# lcd232.net
KiCad netlist of a schematic drawn in EAGLE
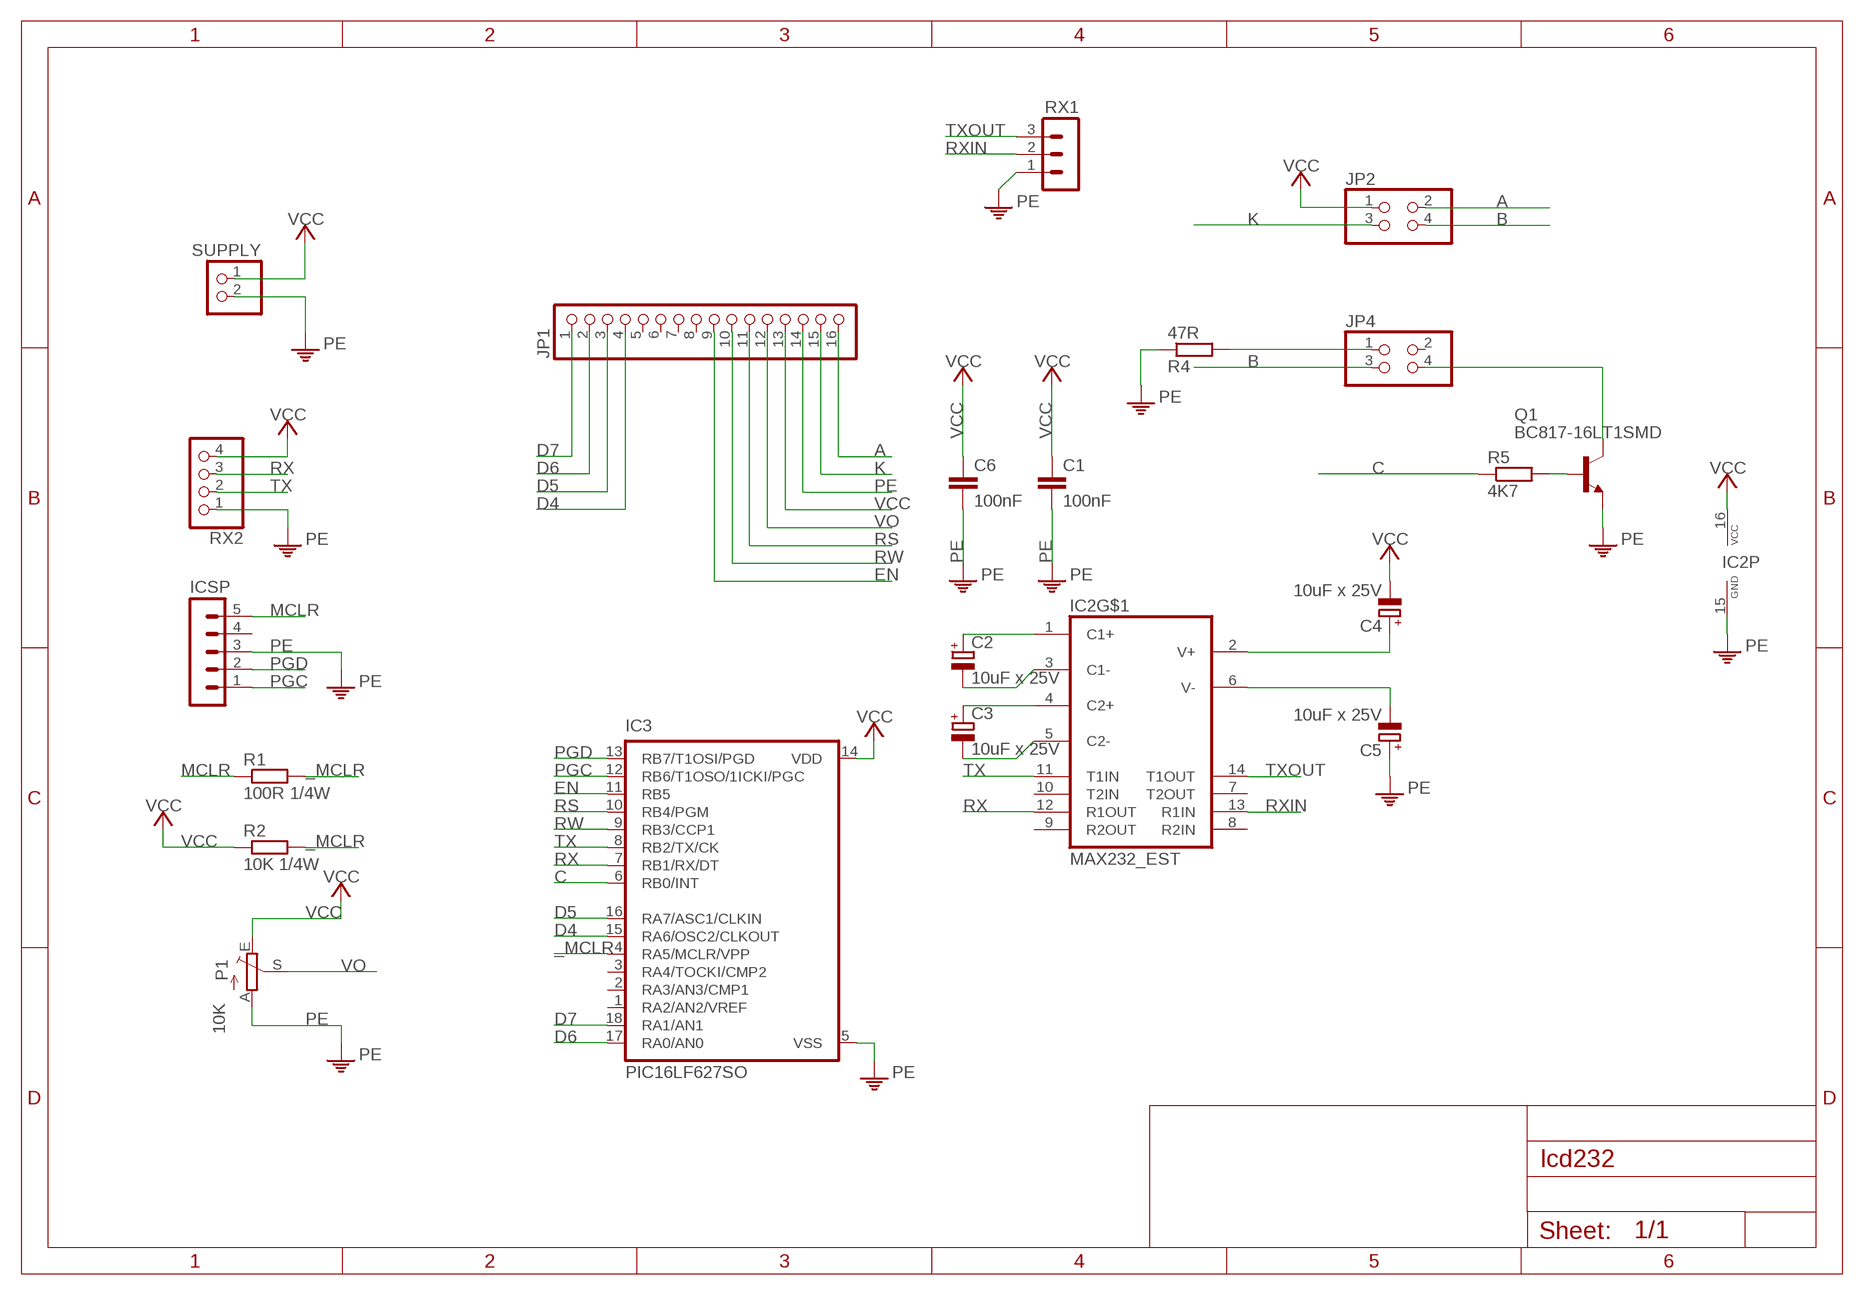
[diagram p0: schematic, sheet 1]

(export (version "E")
  (design (tool "Eeschema 10.0.6"))
  (components
    (comp (ref "C1")
      (value "100nF")
      (footprint "eagle-import:C0805")
      (libsource (lib "eagle-import") (part "C-EUC0805"))
    )
    (comp (ref "C2")
      (value "10uF x 25V")
      (footprint "eagle-import:E2-4")
      (libsource (lib "eagle-import") (part "CPOL-EUE2-4"))
    )
    (comp (ref "C3")
      (value "10uF x 25V")
      (footprint "eagle-import:E2-4")
      (libsource (lib "eagle-import") (part "CPOL-EUE2-4"))
    )
    (comp (ref "C4")
      (value "10uF x 25V")
      (footprint "eagle-import:E2-4")
      (libsource (lib "eagle-import") (part "CPOL-EUE2-4"))
    )
    (comp (ref "C5")
      (value "10uF x 25V")
      (footprint "eagle-import:E2-4")
      (libsource (lib "eagle-import") (part "CPOL-EUE2-4"))
    )
    (comp (ref "C6")
      (value "100nF")
      (footprint "eagle-import:C0805")
      (libsource (lib "eagle-import") (part "C-EUC0805"))
    )
    (comp (ref "IC2")
      (value "MAX232_EST")
      (footprint "eagle-import:SO16_EST")
      (libsource (lib "eagle-import") (part "MAX232_EST"))
    )
    (comp (ref "IC3")
      (value "PIC16LF627SO")
      (footprint "eagle-import:SO-18W")
      (fields (field (name "MF") "MICROCHIP") (field (name "MPN") "PIC16LF627A-I/SO"))
      (libsource (lib "eagle-import") (part "PIC16F627SOL"))
    )
    (comp (ref "ICSP")
      (value "MA05-1")
      (footprint "eagle-import:MA05-1")
      (libsource (lib "eagle-import") (part "MA05-1"))
    )
    (comp (ref "JP1")
      (value "PINHD-1X16")
      (footprint "eagle-import:1X16")
      (libsource (lib "eagle-import") (part "PINHD-1X16"))
    )
    (comp (ref "JP2")
      (value "PINHD-2X2")
      (footprint "eagle-import:2X02")
      (libsource (lib "eagle-import") (part "PINHD-2X2"))
    )
    (comp (ref "JP4")
      (value "PINHD-2X2")
      (footprint "eagle-import:2X02")
      (libsource (lib "eagle-import") (part "PINHD-2X2"))
    )
    (comp (ref "P1")
      (value "10K")
      (footprint "eagle-import:CA9V")
      (libsource (lib "eagle-import") (part "TRIM_EU-CA9V"))
    )
    (comp (ref "Q1")
      (value "BC817-16LT1SMD")
      (footprint "eagle-import:SOT23-BEC")
      (libsource (lib "eagle-import") (part "BC817SMD-16LT1"))
    )
    (comp (ref "R1")
      (value "100R 1/4W")
      (footprint "eagle-import:M0805")
      (libsource (lib "eagle-import") (part "R-EU_M0805"))
    )
    (comp (ref "R2")
      (value "10K 1/4W")
      (footprint "eagle-import:M0805")
      (libsource (lib "eagle-import") (part "R-EU_M0805"))
    )
    (comp (ref "R4")
      (value "47R")
      (footprint "eagle-import:M0805")
      (libsource (lib "eagle-import") (part "R-EU_M0805"))
    )
    (comp (ref "R5")
      (value "4K7")
      (footprint "eagle-import:M0805")
      (libsource (lib "eagle-import") (part "R-EU_M0805"))
    )
    (comp (ref "RX1")
      (value "MA03-1")
      (footprint "eagle-import:MA03-1")
      (fields (field (name "OC_FARNELL") "unknown") (field (name "OC_NEWARK") "unknown"))
      (libsource (lib "eagle-import") (part "MA03-1"))
    )
    (comp (ref "RX2")
      (value "PINHD-1X4")
      (footprint "eagle-import:1X04")
      (libsource (lib "eagle-import") (part "PINHD-1X4"))
    )
    (comp (ref "SUPPLY")
      (value "PINHD-1X2")
      (footprint "eagle-import:1X02")
      (libsource (lib "eagle-import") (part "PINHD-1X2"))
    )
  )
  (nets
    (net (code "1") (name "/A") (class "Default")
      (node (ref "JP1") (pin "16") (pinfunction "16_16") (pintype "passive"))
      (node (ref "JP2") (pin "2") (pinfunction "2_2") (pintype "passive"))
    )
    (net (code "2") (name "/B") (class "Default")
      (node (ref "JP2") (pin "4") (pinfunction "4_4") (pintype "passive"))
      (node (ref "JP4") (pin "3") (pinfunction "3_3") (pintype "passive"))
    )
    (net (code "3") (name "/C") (class "Default")
      (node (ref "IC3") (pin "6") (pinfunction "RB0/INT_6") (pintype "bidirectional"))
      (node (ref "R5") (pin "1") (pinfunction "1_1") (pintype "passive"))
    )
    (net (code "4") (name "/D4") (class "Default")
      (node (ref "IC3") (pin "15") (pinfunction "RA6/OSC2/CLKOUT_15") (pintype "bidirectional"))
      (node (ref "JP1") (pin "4") (pinfunction "4_4") (pintype "passive"))
    )
    (net (code "5") (name "/D5") (class "Default")
      (node (ref "IC3") (pin "16") (pinfunction "RA7/ASC1/CLKIN_16") (pintype "bidirectional"))
      (node (ref "JP1") (pin "3") (pinfunction "3_3") (pintype "passive"))
    )
    (net (code "6") (name "/D6") (class "Default")
      (node (ref "IC3") (pin "17") (pinfunction "RA0/AN0_17") (pintype "bidirectional"))
      (node (ref "JP1") (pin "2") (pinfunction "2_2") (pintype "passive"))
    )
    (net (code "7") (name "/D7") (class "Default")
      (node (ref "IC3") (pin "18") (pinfunction "RA1/AN1_18") (pintype "bidirectional"))
      (node (ref "JP1") (pin "1") (pinfunction "1_1") (pintype "passive"))
    )
    (net (code "8") (name "/EN") (class "Default")
      (node (ref "IC3") (pin "11") (pinfunction "RB5_11") (pintype "bidirectional"))
      (node (ref "JP1") (pin "9") (pinfunction "9_9") (pintype "passive"))
    )
    (net (code "9") (name "/K") (class "Default")
      (node (ref "JP1") (pin "15") (pinfunction "15_15") (pintype "passive"))
      (node (ref "JP2") (pin "3") (pinfunction "3_3") (pintype "passive"))
    )
    (net (code "10") (name "/MCLR") (class "Default")
      (node (ref "ICSP") (pin "5") (pinfunction "5_5") (pintype "passive"))
      (node (ref "R1") (pin "1") (pinfunction "1_1") (pintype "passive"))
    )
    (net (code "11") (name "/PGC") (class "Default")
      (node (ref "IC3") (pin "12") (pinfunction "RB6/T1OSO/1ICKI/PGC_12") (pintype "bidirectional"))
      (node (ref "ICSP") (pin "1") (pinfunction "1_1") (pintype "passive"))
    )
    (net (code "12") (name "/PGD") (class "Default")
      (node (ref "IC3") (pin "13") (pinfunction "RB7/T1OSI/PGD_13") (pintype "bidirectional"))
      (node (ref "ICSP") (pin "2") (pinfunction "2_2") (pintype "passive"))
    )
    (net (code "13") (name "/RS") (class "Default")
      (node (ref "IC3") (pin "10") (pinfunction "RB4/PGM_10") (pintype "bidirectional"))
      (node (ref "JP1") (pin "11") (pinfunction "11_11") (pintype "passive"))
    )
    (net (code "14") (name "/RW") (class "Default")
      (node (ref "IC3") (pin "9") (pinfunction "RB3/CCP1_9") (pintype "bidirectional"))
      (node (ref "JP1") (pin "10") (pinfunction "10_10") (pintype "passive"))
    )
    (net (code "15") (name "/RX") (class "Default")
      (node (ref "IC2") (pin "12") (pinfunction "R1OUT_12") (pintype "output"))
      (node (ref "IC3") (pin "7") (pinfunction "RB1/RX/DT_7") (pintype "bidirectional"))
      (node (ref "RX2") (pin "3") (pinfunction "3_3") (pintype "passive"))
    )
    (net (code "16") (name "/RXIN") (class "Default")
      (node (ref "IC2") (pin "13") (pinfunction "R1IN_13") (pintype "input"))
      (node (ref "RX1") (pin "2") (pinfunction "2_2") (pintype "passive"))
    )
    (net (code "17") (name "/TX") (class "Default")
      (node (ref "IC2") (pin "11") (pinfunction "T1IN_11") (pintype "input"))
      (node (ref "IC3") (pin "8") (pinfunction "RB2/TX/CK_8") (pintype "bidirectional"))
      (node (ref "RX2") (pin "2") (pinfunction "2_2") (pintype "passive"))
    )
    (net (code "18") (name "/TXOUT") (class "Default")
      (node (ref "IC2") (pin "14") (pinfunction "T1OUT_14") (pintype "output"))
      (node (ref "RX1") (pin "3") (pinfunction "3_3") (pintype "passive"))
    )
    (net (code "19") (name "/VO") (class "Default")
      (node (ref "JP1") (pin "12") (pinfunction "12_12") (pintype "passive"))
      (node (ref "P1") (pin "S") (pinfunction "S_S") (pintype "passive"))
    )
    (net (code "20") (name "/_MCLR") (class "Default")
      (node (ref "IC3") (pin "4") (pinfunction "RA5/MCLR/VPP_4") (pintype "input"))
      (node (ref "R1") (pin "2") (pinfunction "2_2") (pintype "passive"))
      (node (ref "R2") (pin "2") (pinfunction "2_2") (pintype "passive"))
    )
    (net (code "21") (name "Net-(IC2A-C1+)") (class "Default")
      (node (ref "C2") (pin "+") (pinfunction "+_+") (pintype "passive"))
      (node (ref "IC2") (pin "1") (pinfunction "C1+_1") (pintype "bidirectional"))
    )
    (net (code "22") (name "Net-(IC2A-C1-)") (class "Default")
      (node (ref "C2") (pin "-") (pinfunction "-_-") (pintype "passive"))
      (node (ref "IC2") (pin "3") (pinfunction "C1-_3") (pintype "bidirectional"))
    )
    (net (code "23") (name "Net-(IC2A-C2+)") (class "Default")
      (node (ref "C3") (pin "+") (pinfunction "+_+") (pintype "passive"))
      (node (ref "IC2") (pin "4") (pinfunction "C2+_4") (pintype "bidirectional"))
    )
    (net (code "24") (name "Net-(IC2A-C2-)") (class "Default")
      (node (ref "C3") (pin "-") (pinfunction "-_-") (pintype "passive"))
      (node (ref "IC2") (pin "5") (pinfunction "C2-_5") (pintype "bidirectional"))
    )
    (net (code "25") (name "Net-(IC2A-V+)") (class "Default")
      (node (ref "C4") (pin "+") (pinfunction "+_+") (pintype "passive"))
      (node (ref "IC2") (pin "2") (pinfunction "V+_2") (pintype "bidirectional"))
    )
    (net (code "26") (name "Net-(IC2A-V-)") (class "Default")
      (node (ref "C5") (pin "-") (pinfunction "-_-") (pintype "passive"))
      (node (ref "IC2") (pin "6") (pinfunction "V-_6") (pintype "bidirectional"))
    )
    (net (code "27") (name "Net-(JP4-Pad1)") (class "Default")
      (node (ref "JP4") (pin "1") (pinfunction "1_1") (pintype "passive"))
      (node (ref "R4") (pin "2") (pinfunction "2_2") (pintype "passive"))
    )
    (net (code "28") (name "Net-(JP4-Pad4)") (class "Default")
      (node (ref "JP4") (pin "4") (pinfunction "4_4") (pintype "passive"))
      (node (ref "Q1") (pin "C") (pinfunction "C_C") (pintype "passive"))
    )
    (net (code "29") (name "Net-(Q1-PadB)") (class "Default")
      (node (ref "Q1") (pin "B") (pinfunction "B_B") (pintype "passive"))
      (node (ref "R5") (pin "2") (pinfunction "2_2") (pintype "passive"))
    )
    (net (code "30") (name "PE") (class "Default")
      (node (ref "C1") (pin "2") (pinfunction "2_2") (pintype "passive"))
      (node (ref "C5") (pin "+") (pinfunction "+_+") (pintype "passive"))
      (node (ref "C6") (pin "2") (pinfunction "2_2") (pintype "passive"))
      (node (ref "IC2") (pin "15") (pinfunction "GND_15") (pintype "power_in"))
      (node (ref "IC3") (pin "5") (pinfunction "VSS_5") (pintype "power_in"))
      (node (ref "ICSP") (pin "3") (pinfunction "3_3") (pintype "passive"))
      (node (ref "JP1") (pin "14") (pinfunction "14_14") (pintype "passive"))
      (node (ref "P1") (pin "A") (pinfunction "A_A") (pintype "passive"))
      (node (ref "Q1") (pin "E") (pinfunction "E_E") (pintype "passive"))
      (node (ref "R4") (pin "1") (pinfunction "1_1") (pintype "passive"))
      (node (ref "RX1") (pin "1") (pinfunction "1_1") (pintype "passive"))
      (node (ref "RX2") (pin "1") (pinfunction "1_1") (pintype "passive"))
      (node (ref "SUPPLY") (pin "2") (pinfunction "2_2") (pintype "passive"))
    )
    (net (code "31") (name "VCC") (class "Default")
      (node (ref "C1") (pin "1") (pinfunction "1_1") (pintype "passive"))
      (node (ref "C4") (pin "-") (pinfunction "-_-") (pintype "passive"))
      (node (ref "C6") (pin "1") (pinfunction "1_1") (pintype "passive"))
      (node (ref "IC2") (pin "16") (pinfunction "VCC_16") (pintype "power_in"))
      (node (ref "IC3") (pin "14") (pinfunction "VDD_14") (pintype "power_in"))
      (node (ref "JP1") (pin "13") (pinfunction "13_13") (pintype "passive"))
      (node (ref "JP2") (pin "1") (pinfunction "1_1") (pintype "passive"))
      (node (ref "P1") (pin "E") (pinfunction "E_E") (pintype "passive"))
      (node (ref "R2") (pin "1") (pinfunction "1_1") (pintype "passive"))
      (node (ref "RX2") (pin "4") (pinfunction "4_4") (pintype "passive"))
      (node (ref "SUPPLY") (pin "1") (pinfunction "1_1") (pintype "passive"))
    )
    (net (code "32") (name "unconnected-(IC2A-R2IN-Pad8)") (class "Default")
      (node (ref "IC2") (pin "8") (pinfunction "R2IN_8") (pintype "input"))
    )
    (net (code "33") (name "unconnected-(IC2A-R2OUT-Pad9)") (class "Default")
      (node (ref "IC2") (pin "9") (pinfunction "R2OUT_9") (pintype "output"))
    )
    (net (code "34") (name "unconnected-(IC2A-T2IN-Pad10)") (class "Default")
      (node (ref "IC2") (pin "10") (pinfunction "T2IN_10") (pintype "input"))
    )
    (net (code "35") (name "unconnected-(IC2A-T2OUT-Pad7)") (class "Default")
      (node (ref "IC2") (pin "7") (pinfunction "T2OUT_7") (pintype "output"))
    )
    (net (code "36") (name "unconnected-(IC3-RA2{slash}AN2{slash}VREF-Pad1)") (class "Default")
      (node (ref "IC3") (pin "1") (pinfunction "RA2/AN2/VREF_1") (pintype "bidirectional"))
    )
    (net (code "37") (name "unconnected-(IC3-RA3{slash}AN3{slash}CMP1-Pad2)") (class "Default")
      (node (ref "IC3") (pin "2") (pinfunction "RA3/AN3/CMP1_2") (pintype "bidirectional"))
    )
    (net (code "38") (name "unconnected-(IC3-RA4{slash}TOCKI{slash}CMP2-Pad3)") (class "Default")
      (node (ref "IC3") (pin "3") (pinfunction "RA4/TOCKI/CMP2_3") (pintype "bidirectional"))
    )
    (net (code "39") (name "unconnected-(ICSP-Pad4)") (class "Default")
      (node (ref "ICSP") (pin "4") (pinfunction "4_4") (pintype "passive"))
    )
    (net (code "40") (name "unconnected-(JP1-Pad5)") (class "Default")
      (node (ref "JP1") (pin "5") (pinfunction "5_5") (pintype "passive"))
    )
    (net (code "41") (name "unconnected-(JP1-Pad6)") (class "Default")
      (node (ref "JP1") (pin "6") (pinfunction "6_6") (pintype "passive"))
    )
    (net (code "42") (name "unconnected-(JP1-Pad7)") (class "Default")
      (node (ref "JP1") (pin "7") (pinfunction "7_7") (pintype "passive"))
    )
    (net (code "43") (name "unconnected-(JP1-Pad8)") (class "Default")
      (node (ref "JP1") (pin "8") (pinfunction "8_8") (pintype "passive"))
    )
    (net (code "44") (name "unconnected-(JP4-Pad2)") (class "Default")
      (node (ref "JP4") (pin "2") (pinfunction "2_2") (pintype "passive"))
    )
  )
)
